# inverter.net
KiCad netlist of a schematic drawn in Altium Designer
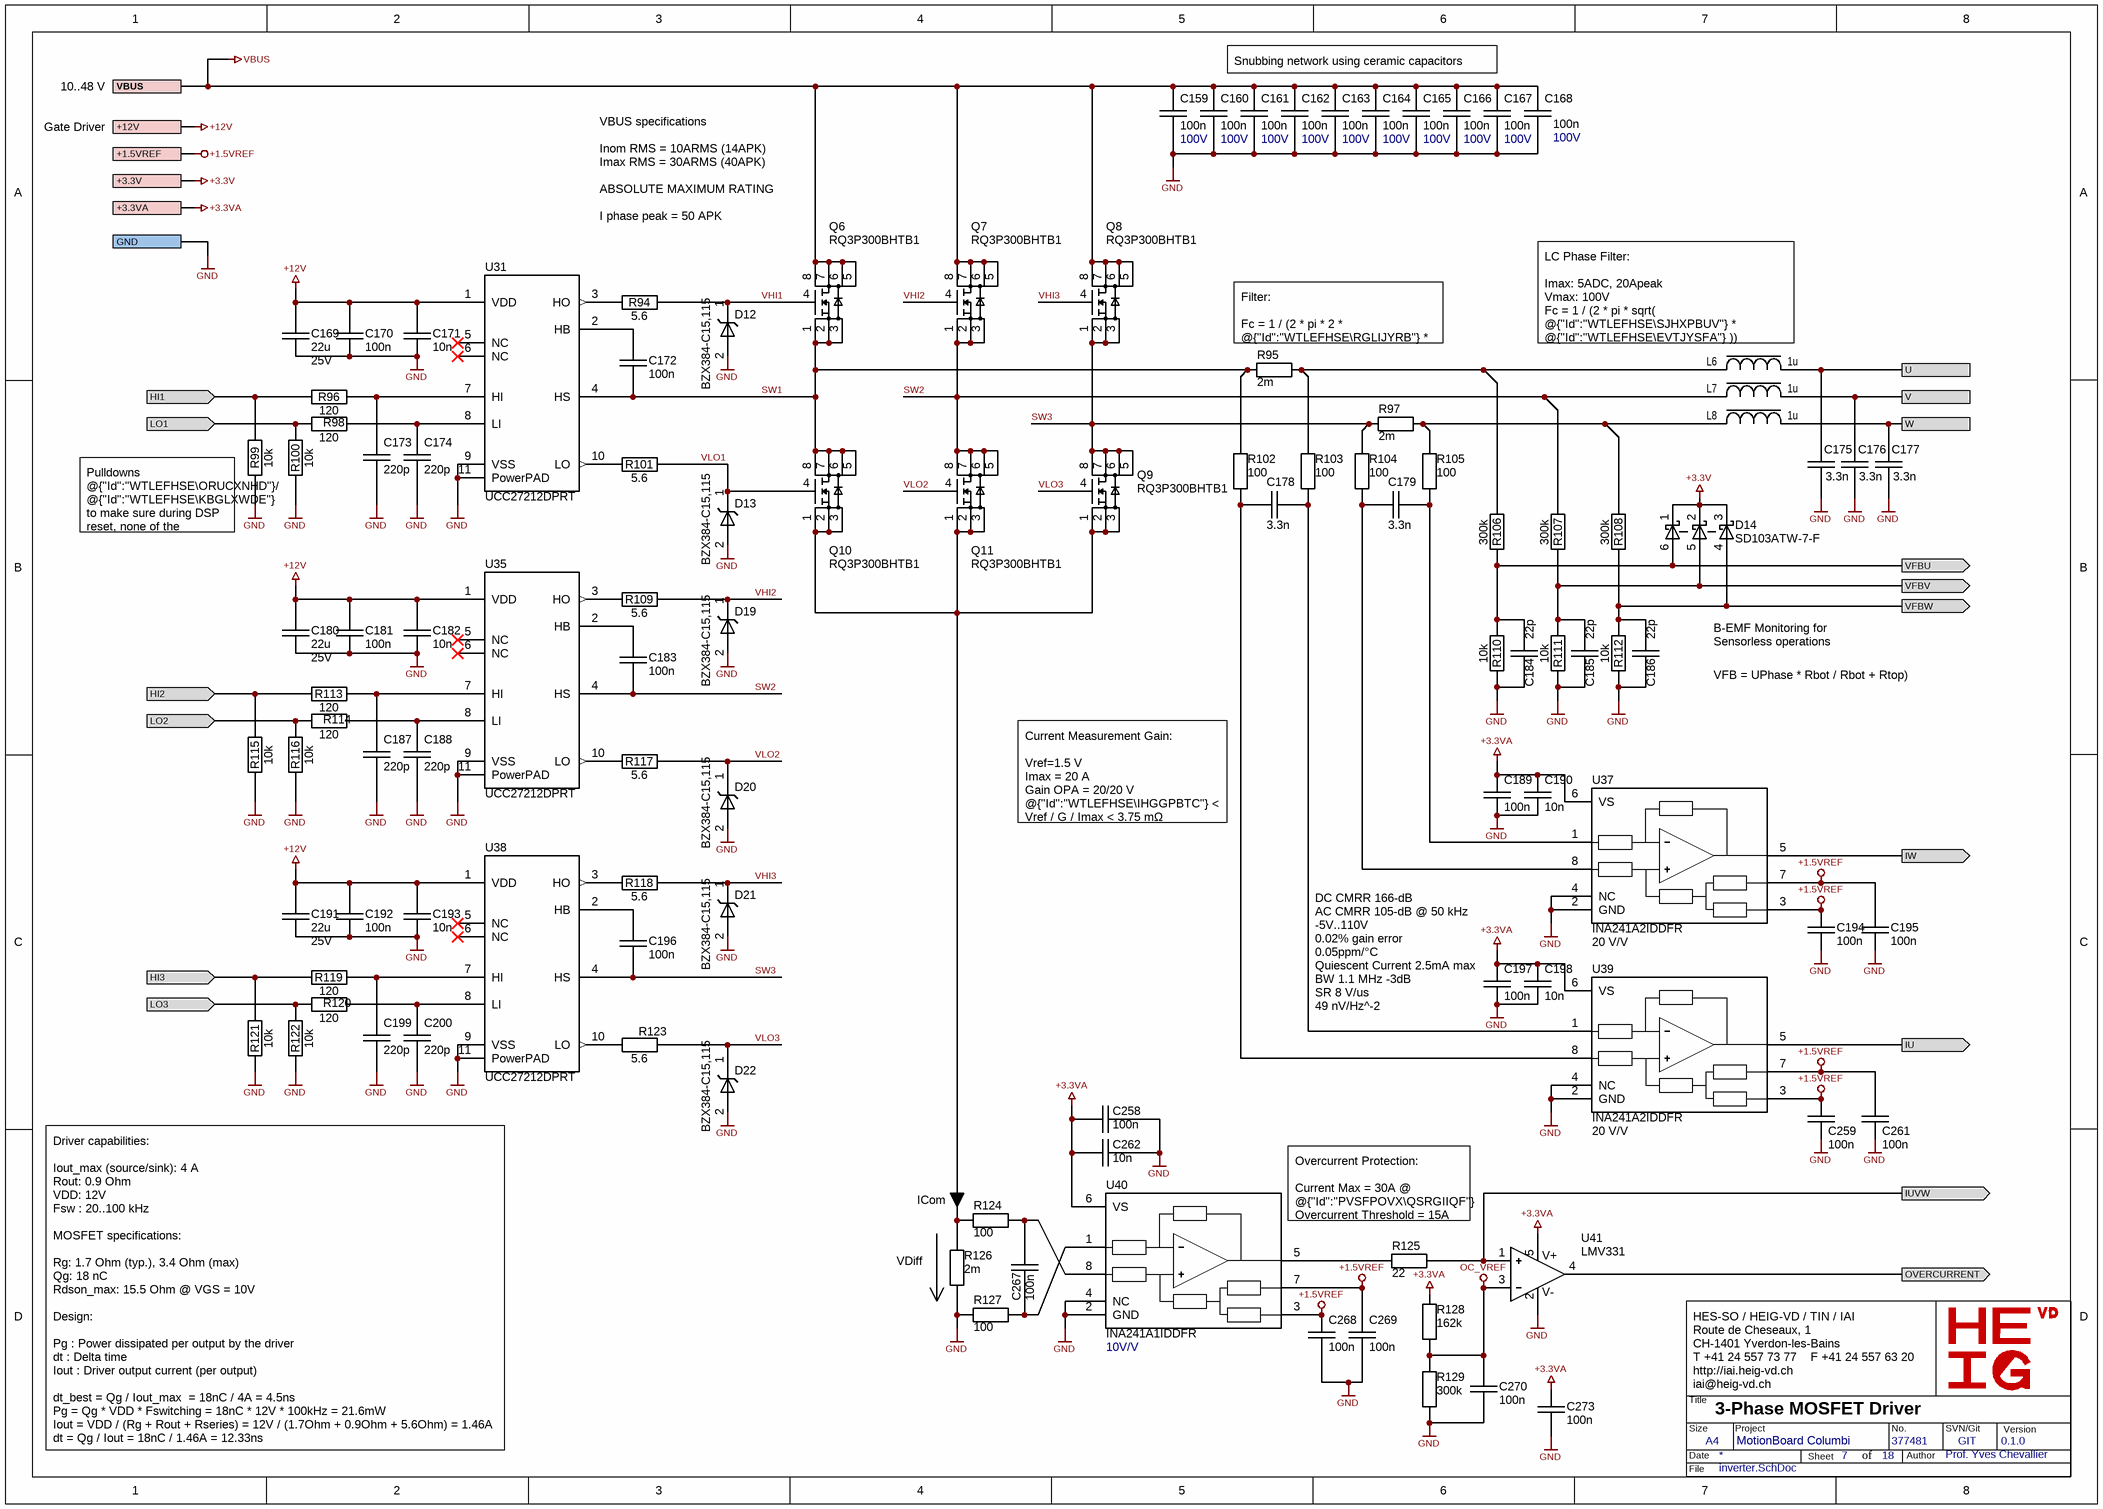
[diagram p0: inverter.SchDoc]

(export (version "E")
  (design (tool "Eeschema 10.0.6"))
  (components
    (comp (ref "C159")
      (value "100n")
      (footprint "SM/C1206")
      (description "100 nF ±5% 100V Ceramic Capacitor C0G, NP0 1206 (3216 Metric)")
      (fields (field (name "VOLTAGE") "100V"))
      (libsource (lib "motionboard") (part "CAP CER 100NF 100V C0G 1206"))
    )
    (comp (ref "C160")
      (value "100n")
      (footprint "SM/C1206")
      (description "100 nF ±5% 100V Ceramic Capacitor C0G, NP0 1206 (3216 Metric)")
      (fields (field (name "VOLTAGE") "100V"))
      (libsource (lib "motionboard") (part "CAP CER 100NF 100V C0G 1206"))
    )
    (comp (ref "C161")
      (value "100n")
      (footprint "SM/C1206")
      (description "100 nF ±5% 100V Ceramic Capacitor C0G, NP0 1206 (3216 Metric)")
      (fields (field (name "VOLTAGE") "100V"))
      (libsource (lib "motionboard") (part "CAP CER 100NF 100V C0G 1206"))
    )
    (comp (ref "C162")
      (value "100n")
      (footprint "SM/C1206")
      (description "100 nF ±5% 100V Ceramic Capacitor C0G, NP0 1206 (3216 Metric)")
      (fields (field (name "VOLTAGE") "100V"))
      (libsource (lib "motionboard") (part "CAP CER 100NF 100V C0G 1206"))
    )
    (comp (ref "C163")
      (value "100n")
      (footprint "SM/C1206")
      (description "100 nF ±5% 100V Ceramic Capacitor C0G, NP0 1206 (3216 Metric)")
      (fields (field (name "VOLTAGE") "100V"))
      (libsource (lib "motionboard") (part "CAP CER 100NF 100V C0G 1206"))
    )
    (comp (ref "C164")
      (value "100n")
      (footprint "SM/C1206")
      (description "100 nF ±5% 100V Ceramic Capacitor C0G, NP0 1206 (3216 Metric)")
      (fields (field (name "VOLTAGE") "100V"))
      (libsource (lib "motionboard") (part "CAP CER 100NF 100V C0G 1206"))
    )
    (comp (ref "C165")
      (value "100n")
      (footprint "SM/C1206")
      (description "100 nF ±5% 100V Ceramic Capacitor C0G, NP0 1206 (3216 Metric)")
      (fields (field (name "VOLTAGE") "100V"))
      (libsource (lib "motionboard") (part "CAP CER 100NF 100V C0G 1206"))
    )
    (comp (ref "C166")
      (value "100n")
      (footprint "SM/C1206")
      (description "100 nF ±5% 100V Ceramic Capacitor C0G, NP0 1206 (3216 Metric)")
      (fields (field (name "VOLTAGE") "100V"))
      (libsource (lib "motionboard") (part "CAP CER 100NF 100V C0G 1206"))
    )
    (comp (ref "C167")
      (value "100n")
      (footprint "SM/C1206")
      (description "100 nF ±5% 100V Ceramic Capacitor C0G, NP0 1206 (3216 Metric)")
      (fields (field (name "VOLTAGE") "100V"))
      (libsource (lib "motionboard") (part "CAP CER 100NF 100V C0G 1206"))
    )
    (comp (ref "C168")
      (value "100n")
      (footprint "SM/C1206")
      (description "100 nF ±5% 100V Ceramic Capacitor C0G, NP0 1206 (3216 Metric)")
      (fields (field (name "VOLTAGE") "100V"))
      (libsource (lib "motionboard") (part "CAP CER 100NF 100V C0G 1206"))
    )
    (comp (ref "C169")
      (value "22u")
      (footprint "SM/C0805")
      (description "22 µF ±20% 25V Ceramic Capacitor X5R 0805 (2012 Metric)")
      (fields (field (name "VOLTAGE") "25V"))
      (libsource (lib "motionboard") (part "CAP CER 22UF 25V X5R 0805"))
    )
    (comp (ref "C170")
      (value "100n")
      (footprint "SM/C0402")
      (description "100 nF ±10% 25V Ceramic Capacitor X5R 0402 (1005 Metric)")
      (fields (field (name "VOLTAGE") "25V"))
      (libsource (lib "motionboard") (part "CAP CER 100NF 25V X5R 0402"))
    )
    (comp (ref "C171")
      (value "10n")
      (footprint "SM/C0402")
      (description "10 nF ±10% 50V Ceramic Capacitor X7R 0402 (1005 Metric)")
      (fields (field (name "VOLTAGE") "50V"))
      (libsource (lib "motionboard") (part "CAP CER 10NF 50V X7R 0402"))
    )
    (comp (ref "C172")
      (value "100n")
      (footprint "SM/C0402")
      (description "100 nF ±10% 25V Ceramic Capacitor X5R 0402 (1005 Metric)")
      (fields (field (name "VOLTAGE") "25V"))
      (libsource (lib "motionboard") (part "CAP CER 100NF 25V X5R 0402"))
    )
    (comp (ref "C173")
      (value "220p")
      (footprint "SM/C0402")
      (description "220 pF ±5% 50V Ceramic Capacitor C0G, NP0 0402 (1005 Metric)")
      (fields (field (name "VOLTAGE") "50V"))
      (libsource (lib "motionboard") (part "CAP CER 220PF 50V C0G/NP0 0402"))
    )
    (comp (ref "C174")
      (value "220p")
      (footprint "SM/C0402")
      (description "220 pF ±5% 50V Ceramic Capacitor C0G, NP0 0402 (1005 Metric)")
      (fields (field (name "VOLTAGE") "50V"))
      (libsource (lib "motionboard") (part "CAP CER 220PF 50V C0G/NP0 0402"))
    )
    (comp (ref "C175")
      (value "3.3n")
      (footprint "SM/C0402")
      (description "3.3 nF ±10% 100V Ceramic Capacitor X8R 0402 (1005 Metric)")
      (fields (field (name "VOLTAGE") "16V"))
      (libsource (lib "motionboard") (part "CAP CER 3.3NF 100V X8R 0402"))
    )
    (comp (ref "C176")
      (value "3.3n")
      (footprint "SM/C0402")
      (description "3.3 nF ±10% 100V Ceramic Capacitor X8R 0402 (1005 Metric)")
      (fields (field (name "VOLTAGE") "16V"))
      (libsource (lib "motionboard") (part "CAP CER 3.3NF 100V X8R 0402"))
    )
    (comp (ref "C177")
      (value "3.3n")
      (footprint "SM/C0402")
      (description "3.3 nF ±10% 100V Ceramic Capacitor X8R 0402 (1005 Metric)")
      (fields (field (name "VOLTAGE") "16V"))
      (libsource (lib "motionboard") (part "CAP CER 3.3NF 100V X8R 0402"))
    )
    (comp (ref "C178")
      (value "3.3n")
      (footprint "SM/C0402")
      (description "3.3 nF ±10% 100V Ceramic Capacitor X8R 0402 (1005 Metric)")
      (fields (field (name "VOLTAGE") "16V"))
      (libsource (lib "motionboard") (part "CAP CER 3.3NF 100V X8R 0402"))
    )
    (comp (ref "C179")
      (value "3.3n")
      (footprint "SM/C0402")
      (description "3.3 nF ±10% 100V Ceramic Capacitor X8R 0402 (1005 Metric)")
      (fields (field (name "VOLTAGE") "16V"))
      (libsource (lib "motionboard") (part "CAP CER 3.3NF 100V X8R 0402"))
    )
    (comp (ref "C180")
      (value "22u")
      (footprint "SM/C0805")
      (description "22 µF ±20% 25V Ceramic Capacitor X5R 0805 (2012 Metric)")
      (fields (field (name "VOLTAGE") "25V"))
      (libsource (lib "motionboard") (part "CAP CER 22UF 25V X5R 0805"))
    )
    (comp (ref "C181")
      (value "100n")
      (footprint "SM/C0402")
      (description "100 nF ±10% 25V Ceramic Capacitor X5R 0402 (1005 Metric)")
      (fields (field (name "VOLTAGE") "25V"))
      (libsource (lib "motionboard") (part "CAP CER 100NF 25V X5R 0402"))
    )
    (comp (ref "C182")
      (value "10n")
      (footprint "SM/C0402")
      (description "10 nF ±10% 50V Ceramic Capacitor X7R 0402 (1005 Metric)")
      (fields (field (name "VOLTAGE") "50V"))
      (libsource (lib "motionboard") (part "CAP CER 10NF 50V X7R 0402"))
    )
    (comp (ref "C183")
      (value "100n")
      (footprint "SM/C0402")
      (description "100 nF ±10% 25V Ceramic Capacitor X5R 0402 (1005 Metric)")
      (fields (field (name "VOLTAGE") "25V"))
      (libsource (lib "motionboard") (part "CAP CER 100NF 25V X5R 0402"))
    )
    (comp (ref "C184")
      (value "22p")
      (footprint "SM/C0402")
      (description "22 pF ±2% 50V Ceramic Capacitor C0G, NP0 0402 (1005 Metric)")
      (fields (field (name "VOLTAGE") "50V"))
      (libsource (lib "motionboard") (part "CAP CER 22PF 50V C0G/NPO 0402"))
    )
    (comp (ref "C185")
      (value "22p")
      (footprint "SM/C0402")
      (description "22 pF ±2% 50V Ceramic Capacitor C0G, NP0 0402 (1005 Metric)")
      (fields (field (name "VOLTAGE") "50V"))
      (libsource (lib "motionboard") (part "CAP CER 22PF 50V C0G/NPO 0402"))
    )
    (comp (ref "C186")
      (value "22p")
      (footprint "SM/C0402")
      (description "22 pF ±2% 50V Ceramic Capacitor C0G, NP0 0402 (1005 Metric)")
      (fields (field (name "VOLTAGE") "50V"))
      (libsource (lib "motionboard") (part "CAP CER 22PF 50V C0G/NPO 0402"))
    )
    (comp (ref "C187")
      (value "220p")
      (footprint "SM/C0402")
      (description "220 pF ±5% 50V Ceramic Capacitor C0G, NP0 0402 (1005 Metric)")
      (fields (field (name "VOLTAGE") "50V"))
      (libsource (lib "motionboard") (part "CAP CER 220PF 50V C0G/NP0 0402"))
    )
    (comp (ref "C188")
      (value "220p")
      (footprint "SM/C0402")
      (description "220 pF ±5% 50V Ceramic Capacitor C0G, NP0 0402 (1005 Metric)")
      (fields (field (name "VOLTAGE") "50V"))
      (libsource (lib "motionboard") (part "CAP CER 220PF 50V C0G/NP0 0402"))
    )
    (comp (ref "C189")
      (value "100n")
      (footprint "SM/C0402")
      (description "100 nF ±10% 25V Ceramic Capacitor X5R 0402 (1005 Metric)")
      (fields (field (name "VOLTAGE") "25V"))
      (libsource (lib "motionboard") (part "CAP CER 100NF 25V X5R 0402"))
    )
    (comp (ref "C190")
      (value "10n")
      (footprint "SM/C0402")
      (description "10 nF ±10% 50V Ceramic Capacitor X7R 0402 (1005 Metric)")
      (fields (field (name "VOLTAGE") "50V"))
      (libsource (lib "motionboard") (part "CAP CER 10NF 50V X7R 0402"))
    )
    (comp (ref "C191")
      (value "22u")
      (footprint "SM/C0805")
      (description "22 µF ±20% 25V Ceramic Capacitor X5R 0805 (2012 Metric)")
      (fields (field (name "VOLTAGE") "25V"))
      (libsource (lib "motionboard") (part "CAP CER 22UF 25V X5R 0805"))
    )
    (comp (ref "C192")
      (value "100n")
      (footprint "SM/C0402")
      (description "100 nF ±10% 25V Ceramic Capacitor X5R 0402 (1005 Metric)")
      (fields (field (name "VOLTAGE") "25V"))
      (libsource (lib "motionboard") (part "CAP CER 100NF 25V X5R 0402"))
    )
    (comp (ref "C193")
      (value "10n")
      (footprint "SM/C0402")
      (description "10 nF ±10% 50V Ceramic Capacitor X7R 0402 (1005 Metric)")
      (fields (field (name "VOLTAGE") "50V"))
      (libsource (lib "motionboard") (part "CAP CER 10NF 50V X7R 0402"))
    )
    (comp (ref "C194")
      (value "100n")
      (footprint "SM/C0402")
      (description "100 nF ±10% 25V Ceramic Capacitor X5R 0402 (1005 Metric)")
      (fields (field (name "VOLTAGE") "25V"))
      (libsource (lib "motionboard") (part "CAP CER 100NF 25V X5R 0402"))
    )
    (comp (ref "C195")
      (value "100n")
      (footprint "SM/C0402")
      (description "100 nF ±10% 25V Ceramic Capacitor X5R 0402 (1005 Metric)")
      (fields (field (name "VOLTAGE") "25V"))
      (libsource (lib "motionboard") (part "CAP CER 100NF 25V X5R 0402"))
    )
    (comp (ref "C196")
      (value "100n")
      (footprint "SM/C0402")
      (description "100 nF ±10% 25V Ceramic Capacitor X5R 0402 (1005 Metric)")
      (fields (field (name "VOLTAGE") "25V"))
      (libsource (lib "motionboard") (part "CAP CER 100NF 25V X5R 0402"))
    )
    (comp (ref "C197")
      (value "100n")
      (footprint "SM/C0402")
      (description "100 nF ±10% 25V Ceramic Capacitor X5R 0402 (1005 Metric)")
      (fields (field (name "VOLTAGE") "25V"))
      (libsource (lib "motionboard") (part "CAP CER 100NF 25V X5R 0402"))
    )
    (comp (ref "C198")
      (value "10n")
      (footprint "SM/C0402")
      (description "10 nF ±10% 50V Ceramic Capacitor X7R 0402 (1005 Metric)")
      (fields (field (name "VOLTAGE") "50V"))
      (libsource (lib "motionboard") (part "CAP CER 10NF 50V X7R 0402"))
    )
    (comp (ref "C199")
      (value "220p")
      (footprint "SM/C0402")
      (description "220 pF ±5% 50V Ceramic Capacitor C0G, NP0 0402 (1005 Metric)")
      (fields (field (name "VOLTAGE") "50V"))
      (libsource (lib "motionboard") (part "CAP CER 220PF 50V C0G/NP0 0402"))
    )
    (comp (ref "C200")
      (value "220p")
      (footprint "SM/C0402")
      (description "220 pF ±5% 50V Ceramic Capacitor C0G, NP0 0402 (1005 Metric)")
      (fields (field (name "VOLTAGE") "50V"))
      (libsource (lib "motionboard") (part "CAP CER 220PF 50V C0G/NP0 0402"))
    )
    (comp (ref "C258")
      (value "100n")
      (footprint "SM/C0402")
      (description "100 nF ±10% 25V Ceramic Capacitor X5R 0402 (1005 Metric)")
      (fields (field (name "VOLTAGE") "25V"))
      (libsource (lib "motionboard") (part "CAP CER 100NF 25V X5R 0402"))
    )
    (comp (ref "C259")
      (value "100n")
      (footprint "SM/C0402")
      (description "100 nF ±10% 25V Ceramic Capacitor X5R 0402 (1005 Metric)")
      (fields (field (name "VOLTAGE") "25V"))
      (libsource (lib "motionboard") (part "CAP CER 100NF 25V X5R 0402"))
    )
    (comp (ref "C261")
      (value "100n")
      (footprint "SM/C0402")
      (description "100 nF ±10% 25V Ceramic Capacitor X5R 0402 (1005 Metric)")
      (fields (field (name "VOLTAGE") "25V"))
      (libsource (lib "motionboard") (part "CAP CER 100NF 25V X5R 0402"))
    )
    (comp (ref "C262")
      (value "10n")
      (footprint "SM/C0402")
      (description "10 nF ±10% 50V Ceramic Capacitor X7R 0402 (1005 Metric)")
      (fields (field (name "VOLTAGE") "50V"))
      (libsource (lib "motionboard") (part "CAP CER 10NF 50V X7R 0402"))
    )
    (comp (ref "C267")
      (value "100n")
      (footprint "SM/C0402")
      (description "100 nF ±10% 25V Ceramic Capacitor X5R 0402 (1005 Metric)")
      (fields (field (name "VOLTAGE") "25V"))
      (libsource (lib "motionboard") (part "CAP CER 100NF 25V X5R 0402"))
    )
    (comp (ref "C268")
      (value "100n")
      (footprint "SM/C0402")
      (description "100 nF ±10% 25V Ceramic Capacitor X5R 0402 (1005 Metric)")
      (fields (field (name "VOLTAGE") "25V"))
      (libsource (lib "motionboard") (part "CAP CER 100NF 25V X5R 0402"))
    )
    (comp (ref "C269")
      (value "100n")
      (footprint "SM/C0402")
      (description "100 nF ±10% 25V Ceramic Capacitor X5R 0402 (1005 Metric)")
      (fields (field (name "VOLTAGE") "25V"))
      (libsource (lib "motionboard") (part "CAP CER 100NF 25V X5R 0402"))
    )
    (comp (ref "C270")
      (value "100n")
      (footprint "SM/C0402")
      (description "100 nF ±10% 25V Ceramic Capacitor X5R 0402 (1005 Metric)")
      (fields (field (name "VOLTAGE") "25V"))
      (libsource (lib "motionboard") (part "CAP CER 100NF 25V X5R 0402"))
    )
    (comp (ref "C273")
      (value "100n")
      (footprint "SM/C0402")
      (description "100 nF ±10% 25V Ceramic Capacitor X5R 0402 (1005 Metric)")
      (fields (field (name "VOLTAGE") "25V"))
      (libsource (lib "motionboard") (part "CAP CER 100NF 25V X5R 0402"))
    )
    (comp (ref "D12")
      (value "BZX384-C15,115")
      (footprint "SODFL250X110-2N")
      (description "Zener Diode 15 V 300 mW ±5% Surface Mount SOD-323")
      (libsource (lib "motionboard") (part "DIODE ZENER 15V 300MW SOD323"))
    )
    (comp (ref "D13")
      (value "BZX384-C15,115")
      (footprint "SODFL250X110-2N")
      (description "Zener Diode 15 V 300 mW ±5% Surface Mount SOD-323")
      (libsource (lib "motionboard") (part "DIODE ZENER 15V 300MW SOD323"))
    )
    (comp (ref "D14")
      (value "SD103ATW-7-F")
      (footprint "SC70-6")
      (libsource (lib "motionboard") (part "SD103ATW-7-F"))
    )
    (comp (ref "D19")
      (value "BZX384-C15,115")
      (footprint "SODFL250X110-2N")
      (description "Zener Diode 15 V 300 mW ±5% Surface Mount SOD-323")
      (libsource (lib "motionboard") (part "DIODE ZENER 15V 300MW SOD323"))
    )
    (comp (ref "D20")
      (value "BZX384-C15,115")
      (footprint "SODFL250X110-2N")
      (description "Zener Diode 15 V 300 mW ±5% Surface Mount SOD-323")
      (libsource (lib "motionboard") (part "DIODE ZENER 15V 300MW SOD323"))
    )
    (comp (ref "D21")
      (value "BZX384-C15,115")
      (footprint "SODFL250X110-2N")
      (description "Zener Diode 15 V 300 mW ±5% Surface Mount SOD-323")
      (libsource (lib "motionboard") (part "DIODE ZENER 15V 300MW SOD323"))
    )
    (comp (ref "D22")
      (value "BZX384-C15,115")
      (footprint "SODFL250X110-2N")
      (description "Zener Diode 15 V 300 mW ±5% Surface Mount SOD-323")
      (libsource (lib "motionboard") (part "DIODE ZENER 15V 300MW SOD323"))
    )
    (comp (ref "L6")
      (value "1u")
      (footprint "PA5005.102NLT")
      (description "1 µH Shielded Molded Inductor 20 A 4.52mOhm Max Nonstandard")
      (libsource (lib "motionboard") (part "PA5005.102NLT"))
    )
    (comp (ref "L7")
      (value "1u")
      (footprint "PA5005.102NLT")
      (description "1 µH Shielded Molded Inductor 20 A 4.52mOhm Max Nonstandard")
      (libsource (lib "motionboard") (part "PA5005.102NLT"))
    )
    (comp (ref "L8")
      (value "1u")
      (footprint "PA5005.102NLT")
      (description "1 µH Shielded Molded Inductor 20 A 4.52mOhm Max Nonstandard")
      (libsource (lib "motionboard") (part "PA5005.102NLT"))
    )
    (comp (ref "Q6")
      (value "RQ3P300BHTB1")
      (footprint "RQ3P300BHTB1")
      (description "N-Channel 100 V 39A (Ta) 2W (Ta) Surface Mount 8-HSMT (3.2x3)")
      (libsource (lib "motionboard") (part "RQ3P300BHTB1"))
    )
    (comp (ref "Q7")
      (value "RQ3P300BHTB1")
      (footprint "RQ3P300BHTB1")
      (description "N-Channel 100 V 39A (Ta) 2W (Ta) Surface Mount 8-HSMT (3.2x3)")
      (libsource (lib "motionboard") (part "RQ3P300BHTB1"))
    )
    (comp (ref "Q8")
      (value "RQ3P300BHTB1")
      (footprint "RQ3P300BHTB1")
      (description "N-Channel 100 V 39A (Ta) 2W (Ta) Surface Mount 8-HSMT (3.2x3)")
      (libsource (lib "motionboard") (part "RQ3P300BHTB1"))
    )
    (comp (ref "Q9")
      (value "RQ3P300BHTB1")
      (footprint "RQ3P300BHTB1")
      (description "N-Channel 100 V 39A (Ta) 2W (Ta) Surface Mount 8-HSMT (3.2x3)")
      (libsource (lib "motionboard") (part "RQ3P300BHTB1"))
    )
    (comp (ref "Q10")
      (value "RQ3P300BHTB1")
      (footprint "RQ3P300BHTB1")
      (description "N-Channel 100 V 39A (Ta) 2W (Ta) Surface Mount 8-HSMT (3.2x3)")
      (libsource (lib "motionboard") (part "RQ3P300BHTB1"))
    )
    (comp (ref "Q11")
      (value "RQ3P300BHTB1")
      (footprint "RQ3P300BHTB1")
      (description "N-Channel 100 V 39A (Ta) 2W (Ta) Surface Mount 8-HSMT (3.2x3)")
      (libsource (lib "motionboard") (part "RQ3P300BHTB1"))
    )
    (comp (ref "R94")
      (value "5.6")
      (footprint "SM/R0402")
      (description "5.6 Ohms ±5% 0.063W, 1/16W Chip Resistor 0402 (1005 Metric) Moisture Resistant Thick Film")
      (libsource (lib "motionboard") (part "RES 5.6 OHM 5% 1/16W 0402"))
    )
    (comp (ref "R95")
      (value "2m")
      (footprint "SM/R1206")
      (description "2 mOhms ±1% 1W Chip Resistor 1206 (3216 Metric) Current Sense, Moisture Resistant Metal Element")
      (libsource (lib "motionboard") (part "RES 0.002 OHM 1% 1W 1206"))
    )
    (comp (ref "R96")
      (value "120")
      (footprint "SM/R0402")
      (description "120 Ohms ±1% 0.063W, 1/16W Chip Resistor 0402 (1005 Metric) Moisture Resistant Thick Film")
      (libsource (lib "motionboard") (part "RES 120 OHM 1% 1/16W 0402"))
    )
    (comp (ref "R97")
      (value "2m")
      (footprint "SM/R1206")
      (description "2 mOhms ±1% 1W Chip Resistor 1206 (3216 Metric) Current Sense, Moisture Resistant Metal Element")
      (libsource (lib "motionboard") (part "RES 0.002 OHM 1% 1W 1206"))
    )
    (comp (ref "R98")
      (value "120")
      (footprint "SM/R0402")
      (description "120 Ohms ±1% 0.063W, 1/16W Chip Resistor 0402 (1005 Metric) Moisture Resistant Thick Film")
      (libsource (lib "motionboard") (part "RES 120 OHM 1% 1/16W 0402"))
    )
    (comp (ref "R99")
      (value "10k")
      (footprint "SM/R0402")
      (description "10 kOhms ±1% 0.063W, 1/16W Chip Resistor 0402 (1005 Metric) Moisture Resistant Thick Film")
      (libsource (lib "") (part "RES 10K OHM 1% 1/16W 0402_1"))
    )
    (comp (ref "R100")
      (value "10k")
      (footprint "SM/R0402")
      (description "10 kOhms ±1% 0.063W, 1/16W Chip Resistor 0402 (1005 Metric) Moisture Resistant Thick Film")
      (libsource (lib "") (part "RES 10K OHM 1% 1/16W 0402_1"))
    )
    (comp (ref "R101")
      (value "5.6")
      (footprint "SM/R0402")
      (description "5.6 Ohms ±5% 0.063W, 1/16W Chip Resistor 0402 (1005 Metric) Moisture Resistant Thick Film")
      (libsource (lib "") (part "RES 5.6 OHM 5% 1/16W 0402_1"))
    )
    (comp (ref "R102")
      (value "100")
      (footprint "SM/R0402")
      (description "100 Ohms ±1% 0.063W, 1/16W Chip Resistor 0402 (1005 Metric) Moisture Resistant Thick Film")
      (libsource (lib "") (part "RES 100 OHM 1% 1/16W 0402_1"))
    )
    (comp (ref "R103")
      (value "100")
      (footprint "SM/R0402")
      (description "100 Ohms ±1% 0.063W, 1/16W Chip Resistor 0402 (1005 Metric) Moisture Resistant Thick Film")
      (libsource (lib "") (part "RES 100 OHM 1% 1/16W 0402_1"))
    )
    (comp (ref "R104")
      (value "100")
      (footprint "SM/R0402")
      (description "100 Ohms ±1% 0.063W, 1/16W Chip Resistor 0402 (1005 Metric) Moisture Resistant Thick Film")
      (libsource (lib "") (part "RES 100 OHM 1% 1/16W 0402_1"))
    )
    (comp (ref "R105")
      (value "100")
      (footprint "SM/R0402")
      (description "100 Ohms ±1% 0.063W, 1/16W Chip Resistor 0402 (1005 Metric) Moisture Resistant Thick Film")
      (libsource (lib "") (part "RES 100 OHM 1% 1/16W 0402_1"))
    )
    (comp (ref "R106")
      (value "300k")
      (footprint "SM/R0402")
      (description "300 kOhms ±1% 0.063W, 1/16W Chip Resistor 0402 (1005 Metric) Moisture Resistant Thick Film")
      (libsource (lib "motionboard") (part "RES 300K OHM 1% 1/16W 0402"))
    )
    (comp (ref "R107")
      (value "300k")
      (footprint "SM/R0402")
      (description "300 kOhms ±1% 0.063W, 1/16W Chip Resistor 0402 (1005 Metric) Moisture Resistant Thick Film")
      (libsource (lib "motionboard") (part "RES 300K OHM 1% 1/16W 0402"))
    )
    (comp (ref "R108")
      (value "300k")
      (footprint "SM/R0402")
      (description "300 kOhms ±1% 0.063W, 1/16W Chip Resistor 0402 (1005 Metric) Moisture Resistant Thick Film")
      (libsource (lib "motionboard") (part "RES 300K OHM 1% 1/16W 0402"))
    )
    (comp (ref "R109")
      (value "5.6")
      (footprint "SM/R0402")
      (description "5.6 Ohms ±5% 0.063W, 1/16W Chip Resistor 0402 (1005 Metric) Moisture Resistant Thick Film")
      (libsource (lib "motionboard") (part "RES 5.6 OHM 5% 1/16W 0402"))
    )
    (comp (ref "R110")
      (value "10k")
      (footprint "SM/R0402")
      (description "10 kOhms ±1% 0.063W, 1/16W Chip Resistor 0402 (1005 Metric) Moisture Resistant Thick Film")
      (libsource (lib "motionboard") (part "RES 10K OHM 1% 1/16W 0402"))
    )
    (comp (ref "R111")
      (value "10k")
      (footprint "SM/R0402")
      (description "10 kOhms ±1% 0.063W, 1/16W Chip Resistor 0402 (1005 Metric) Moisture Resistant Thick Film")
      (libsource (lib "motionboard") (part "RES 10K OHM 1% 1/16W 0402"))
    )
    (comp (ref "R112")
      (value "10k")
      (footprint "SM/R0402")
      (description "10 kOhms ±1% 0.063W, 1/16W Chip Resistor 0402 (1005 Metric) Moisture Resistant Thick Film")
      (libsource (lib "motionboard") (part "RES 10K OHM 1% 1/16W 0402"))
    )
    (comp (ref "R113")
      (value "120")
      (footprint "SM/R0402")
      (description "120 Ohms ±1% 0.063W, 1/16W Chip Resistor 0402 (1005 Metric) Moisture Resistant Thick Film")
      (libsource (lib "motionboard") (part "RES 120 OHM 1% 1/16W 0402"))
    )
    (comp (ref "R114")
      (value "120")
      (footprint "SM/R0402")
      (description "120 Ohms ±1% 0.063W, 1/16W Chip Resistor 0402 (1005 Metric) Moisture Resistant Thick Film")
      (libsource (lib "motionboard") (part "RES 120 OHM 1% 1/16W 0402"))
    )
    (comp (ref "R115")
      (value "10k")
      (footprint "SM/R0402")
      (description "10 kOhms ±1% 0.063W, 1/16W Chip Resistor 0402 (1005 Metric) Moisture Resistant Thick Film")
      (libsource (lib "") (part "RES 10K OHM 1% 1/16W 0402_1"))
    )
    (comp (ref "R116")
      (value "10k")
      (footprint "SM/R0402")
      (description "10 kOhms ±1% 0.063W, 1/16W Chip Resistor 0402 (1005 Metric) Moisture Resistant Thick Film")
      (libsource (lib "") (part "RES 10K OHM 1% 1/16W 0402_1"))
    )
    (comp (ref "R117")
      (value "5.6")
      (footprint "SM/R0402")
      (description "5.6 Ohms ±5% 0.063W, 1/16W Chip Resistor 0402 (1005 Metric) Moisture Resistant Thick Film")
      (libsource (lib "") (part "RES 5.6 OHM 5% 1/16W 0402_1"))
    )
    (comp (ref "R118")
      (value "5.6")
      (footprint "SM/R0402")
      (description "5.6 Ohms ±5% 0.063W, 1/16W Chip Resistor 0402 (1005 Metric) Moisture Resistant Thick Film")
      (libsource (lib "motionboard") (part "RES 5.6 OHM 5% 1/16W 0402"))
    )
    (comp (ref "R119")
      (value "120")
      (footprint "SM/R0402")
      (description "120 Ohms ±1% 0.063W, 1/16W Chip Resistor 0402 (1005 Metric) Moisture Resistant Thick Film")
      (libsource (lib "motionboard") (part "RES 120 OHM 1% 1/16W 0402"))
    )
    (comp (ref "R120")
      (value "120")
      (footprint "SM/R0402")
      (description "120 Ohms ±1% 0.063W, 1/16W Chip Resistor 0402 (1005 Metric) Moisture Resistant Thick Film")
      (libsource (lib "motionboard") (part "RES 120 OHM 1% 1/16W 0402"))
    )
    (comp (ref "R121")
      (value "10k")
      (footprint "SM/R0402")
      (description "10 kOhms ±1% 0.063W, 1/16W Chip Resistor 0402 (1005 Metric) Moisture Resistant Thick Film")
      (libsource (lib "") (part "RES 10K OHM 1% 1/16W 0402_1"))
    )
    (comp (ref "R122")
      (value "10k")
      (footprint "SM/R0402")
      (description "10 kOhms ±1% 0.063W, 1/16W Chip Resistor 0402 (1005 Metric) Moisture Resistant Thick Film")
      (libsource (lib "") (part "RES 10K OHM 1% 1/16W 0402_1"))
    )
    (comp (ref "R123")
      (value "5.6")
      (footprint "SM/R0402")
      (description "5.6 Ohms ±5% 0.063W, 1/16W Chip Resistor 0402 (1005 Metric) Moisture Resistant Thick Film")
      (libsource (lib "") (part "RES 5.6 OHM 5% 1/16W 0402_1"))
    )
    (comp (ref "R124")
      (value "100")
      (footprint "SM/R0402")
      (description "100 Ohms ±1% 0.063W, 1/16W Chip Resistor 0402 (1005 Metric) Moisture Resistant Thick Film")
      (libsource (lib "motionboard") (part "RES 100 OHM 1% 1/16W 0402"))
    )
    (comp (ref "R125")
      (value "22")
      (footprint "SM/R0402")
      (description "22 Ohms ±1% 0.063W, 1/16W Chip Resistor 0402 (1005 Metric) Moisture Resistant Thick Film")
      (libsource (lib "motionboard") (part "RES 22 OHM 1% 1/16W 0402"))
    )
    (comp (ref "R126")
      (value "2m")
      (footprint "SM/R1206")
      (description "2 mOhms ±1% 1W Chip Resistor 1206 (3216 Metric) Current Sense, Moisture Resistant Metal Element")
      (libsource (lib "") (part "RES 0.002 OHM 1% 1W 1206_1"))
    )
    (comp (ref "R127")
      (value "100")
      (footprint "SM/R0402")
      (description "100 Ohms ±1% 0.063W, 1/16W Chip Resistor 0402 (1005 Metric) Moisture Resistant Thick Film")
      (libsource (lib "motionboard") (part "RES 100 OHM 1% 1/16W 0402"))
    )
    (comp (ref "R128")
      (value "162k")
      (footprint "SM/R0402")
      (description "162 kOhms ±1% 0.063W, 1/16W Chip Resistor 0402 (1005 Metric) Moisture Resistant Thick Film")
      (libsource (lib "motionboard") (part "RES 162K OHM 1% 1/16W 0402"))
    )
    (comp (ref "R129")
      (value "300k")
      (footprint "SM/R0402")
      (description "300 kOhms ±1% 0.063W, 1/16W Chip Resistor 0402 (1005 Metric) Moisture Resistant Thick Film")
      (libsource (lib "motionboard") (part "RES 300K OHM 1% 1/16W 0402"))
    )
    (comp (ref "U31")
      (value "UCC27212DPRT")
      (footprint "PSON80P400X80_HS-11N")
      (description "Half-Bridge Gate Driver IC Non-Inverting 10-WSON (4x4)")
      (libsource (lib "motionboard") (part "UCC27212"))
    )
    (comp (ref "U35")
      (value "UCC27212DPRT")
      (footprint "PSON80P400X80_HS-11N")
      (description "Half-Bridge Gate Driver IC Non-Inverting 10-WSON (4x4)")
      (libsource (lib "motionboard") (part "UCC27212"))
    )
    (comp (ref "U37")
      (value "INA241A2IDDFR")
      (footprint "SOT65P280X110-8N")
      (description "Current Sense Amplifier 1 Circuit Single-Ended TSOT-23-8")
      (fields (field (name "GAIN") "20 V/V"))
      (libsource (lib "motionboard") (part "INA241A2IDDFR"))
    )
    (comp (ref "U38")
      (value "UCC27212DPRT")
      (footprint "PSON80P400X80_HS-11N")
      (description "Half-Bridge Gate Driver IC Non-Inverting 10-WSON (4x4)")
      (libsource (lib "motionboard") (part "UCC27212"))
    )
    (comp (ref "U39")
      (value "INA241A2IDDFR")
      (footprint "SOT65P280X110-8N")
      (description "Current Sense Amplifier 1 Circuit Single-Ended TSOT-23-8")
      (fields (field (name "GAIN") "20 V/V"))
      (libsource (lib "motionboard") (part "INA241A2IDDFR"))
    )
    (comp (ref "U40")
      (value "INA241A1IDDFR")
      (footprint "SOT65P280X110-8N")
      (description "Current Sense Amplifier 10V/V  1 Circuit Single-Ended TSOT-23-8")
      (fields (field (name "GAIN") "10V/V"))
      (libsource (lib "motionboard") (part "INA241A1IDDFR"))
    )
    (comp (ref "U41")
      (value "LMV331")
      (footprint "SOT23-5")
      (description "Comparator General Purpose CMOS, Open-Collector, TTL SOT-23-5")
      (libsource (lib "motionboard") (part "LM331"))
    )
  )
  (nets
    (net (code "1") (name "+1.5VREF") (class "Default")
      (node (ref "C194") (pin "2") (pintype "passive"))
      (node (ref "C195") (pin "2") (pintype "passive"))
      (node (ref "C259") (pin "2") (pintype "passive"))
      (node (ref "C261") (pin "2") (pintype "passive"))
      (node (ref "C268") (pin "2") (pintype "passive"))
      (node (ref "C269") (pin "2") (pintype "passive"))
      (node (ref "U37") (pin "3") (pinfunction "REF2_3") (pintype "passive"))
      (node (ref "U37") (pin "7") (pinfunction "REF1_7") (pintype "passive"))
      (node (ref "U39") (pin "3") (pinfunction "REF2_3") (pintype "passive"))
      (node (ref "U39") (pin "7") (pinfunction "REF1_7") (pintype "passive"))
      (node (ref "U40") (pin "3") (pinfunction "REF2_3") (pintype "passive"))
      (node (ref "U40") (pin "7") (pinfunction "REF1_7") (pintype "passive"))
    )
    (net (code "2") (name "+3.3V") (class "Default")
      (node (ref "D14") (pin "1") (pinfunction "K_1") (pintype "passive"))
      (node (ref "D14") (pin "2") (pinfunction "K_2") (pintype "passive"))
      (node (ref "D14") (pin "3") (pinfunction "K_3") (pintype "passive"))
    )
    (net (code "3") (name "+3.3VA") (class "Default")
      (node (ref "C189") (pin "2") (pintype "passive"))
      (node (ref "C190") (pin "1") (pintype "passive"))
      (node (ref "C197") (pin "2") (pintype "passive"))
      (node (ref "C198") (pin "1") (pintype "passive"))
      (node (ref "C258") (pin "2") (pintype "passive"))
      (node (ref "C262") (pin "1") (pintype "passive"))
      (node (ref "C273") (pin "2") (pintype "passive"))
      (node (ref "R128") (pin "2") (pintype "passive"))
      (node (ref "U37") (pin "6") (pinfunction "VS_6") (pintype "passive"))
      (node (ref "U39") (pin "6") (pinfunction "VS_6") (pintype "passive"))
      (node (ref "U40") (pin "6") (pinfunction "VS_6") (pintype "passive"))
      (node (ref "U41") (pin "5") (pinfunction "V+_5") (pintype "passive"))
    )
    (net (code "4") (name "+12V") (class "Default")
      (node (ref "C169") (pin "2") (pintype "passive"))
      (node (ref "C170") (pin "2") (pintype "passive"))
      (node (ref "C171") (pin "1") (pintype "passive"))
      (node (ref "C180") (pin "2") (pintype "passive"))
      (node (ref "C181") (pin "2") (pintype "passive"))
      (node (ref "C182") (pin "1") (pintype "passive"))
      (node (ref "C191") (pin "2") (pintype "passive"))
      (node (ref "C192") (pin "2") (pintype "passive"))
      (node (ref "C193") (pin "1") (pintype "passive"))
      (node (ref "U31") (pin "1") (pinfunction "VDD_1") (pintype "power_in"))
      (node (ref "U35") (pin "1") (pinfunction "VDD_1") (pintype "power_in"))
      (node (ref "U38") (pin "1") (pinfunction "VDD_1") (pintype "power_in"))
    )
    (net (code "5") (name "/HI1") (class "Default")
      (node (ref "R96") (pin "2") (pintype "passive"))
      (node (ref "R99") (pin "1") (pintype "passive"))
    )
    (net (code "6") (name "/HI2") (class "Default")
      (node (ref "R113") (pin "2") (pintype "passive"))
      (node (ref "R115") (pin "1") (pintype "passive"))
    )
    (net (code "7") (name "/HI3") (class "Default")
      (node (ref "R119") (pin "2") (pintype "passive"))
      (node (ref "R121") (pin "1") (pintype "passive"))
    )
    (net (code "8") (name "/IU") (class "Default")
      (node (ref "U39") (pin "5") (pinfunction "OUT_5") (pintype "passive"))
    )
    (net (code "9") (name "/IUVW") (class "Default")
      (node (ref "R125") (pin "1") (pintype "passive"))
      (node (ref "U41") (pin "1") (pinfunction "IN+_1") (pintype "passive"))
    )
    (net (code "10") (name "/IW") (class "Default")
      (node (ref "U37") (pin "5") (pinfunction "OUT_5") (pintype "passive"))
    )
    (net (code "11") (name "/LO1") (class "Default")
      (node (ref "R100") (pin "1") (pintype "passive"))
      (node (ref "R98") (pin "2") (pintype "passive"))
    )
    (net (code "12") (name "/LO2") (class "Default")
      (node (ref "R114") (pin "2") (pintype "passive"))
      (node (ref "R116") (pin "1") (pintype "passive"))
    )
    (net (code "13") (name "/LO3") (class "Default")
      (node (ref "R120") (pin "2") (pintype "passive"))
      (node (ref "R122") (pin "1") (pintype "passive"))
    )
    (net (code "14") (name "/OVERCURRENT") (class "Default")
      (node (ref "U41") (pin "4") (pinfunction "OUT_4") (pintype "passive"))
    )
    (net (code "15") (name "/SW1") (class "Default")
      (node (ref "C172") (pin "2") (pintype "passive"))
      (node (ref "Q10") (pin "5") (pinfunction "D_5") (pintype "passive"))
      (node (ref "Q10") (pin "6") (pinfunction "D_6") (pintype "passive"))
      (node (ref "Q10") (pin "7") (pinfunction "D_7") (pintype "passive"))
      (node (ref "Q10") (pin "8") (pinfunction "D_8") (pintype "passive"))
      (node (ref "Q6") (pin "1") (pinfunction "S_1") (pintype "passive"))
      (node (ref "Q6") (pin "2") (pinfunction "S_2") (pintype "passive"))
      (node (ref "Q6") (pin "3") (pinfunction "S_3") (pintype "passive"))
      (node (ref "R102") (pin "2") (pintype "passive"))
      (node (ref "R95") (pin "1") (pintype "passive"))
      (node (ref "U31") (pin "4") (pinfunction "HS_4") (pintype "power_in"))
    )
    (net (code "16") (name "/SW2") (class "Default")
      (node (ref "C183") (pin "2") (pintype "passive"))
      (node (ref "L7") (pin "1") (pintype "passive"))
      (node (ref "Q11") (pin "5") (pinfunction "D_5") (pintype "passive"))
      (node (ref "Q11") (pin "6") (pinfunction "D_6") (pintype "passive"))
      (node (ref "Q11") (pin "7") (pinfunction "D_7") (pintype "passive"))
      (node (ref "Q11") (pin "8") (pinfunction "D_8") (pintype "passive"))
      (node (ref "Q7") (pin "1") (pinfunction "S_1") (pintype "passive"))
      (node (ref "Q7") (pin "2") (pinfunction "S_2") (pintype "passive"))
      (node (ref "Q7") (pin "3") (pinfunction "S_3") (pintype "passive"))
      (node (ref "R107") (pin "2") (pintype "passive"))
      (node (ref "U35") (pin "4") (pinfunction "HS_4") (pintype "power_in"))
    )
    (net (code "17") (name "/SW3") (class "Default")
      (node (ref "C196") (pin "2") (pintype "passive"))
      (node (ref "Q8") (pin "1") (pinfunction "S_1") (pintype "passive"))
      (node (ref "Q8") (pin "2") (pinfunction "S_2") (pintype "passive"))
      (node (ref "Q8") (pin "3") (pinfunction "S_3") (pintype "passive"))
      (node (ref "Q9") (pin "5") (pinfunction "D_5") (pintype "passive"))
      (node (ref "Q9") (pin "6") (pinfunction "D_6") (pintype "passive"))
      (node (ref "Q9") (pin "7") (pinfunction "D_7") (pintype "passive"))
      (node (ref "Q9") (pin "8") (pinfunction "D_8") (pintype "passive"))
      (node (ref "R104") (pin "2") (pintype "passive"))
      (node (ref "R97") (pin "1") (pintype "passive"))
      (node (ref "U38") (pin "4") (pinfunction "HS_4") (pintype "power_in"))
    )
    (net (code "18") (name "/U") (class "Default")
      (node (ref "C175") (pin "2") (pintype "passive"))
      (node (ref "L6") (pin "2") (pintype "passive"))
    )
    (net (code "19") (name "/V") (class "Default")
      (node (ref "C176") (pin "2") (pintype "passive"))
      (node (ref "L7") (pin "2") (pintype "passive"))
    )
    (net (code "20") (name "/VFBU") (class "Default")
      (node (ref "C184") (pin "2") (pintype "passive"))
      (node (ref "D14") (pin "6") (pinfunction "A_6") (pintype "passive"))
      (node (ref "R106") (pin "1") (pintype "passive"))
      (node (ref "R110") (pin "2") (pintype "passive"))
    )
    (net (code "21") (name "/VFBV") (class "Default")
      (node (ref "C185") (pin "2") (pintype "passive"))
      (node (ref "D14") (pin "5") (pinfunction "A_5") (pintype "passive"))
      (node (ref "R107") (pin "1") (pintype "passive"))
      (node (ref "R111") (pin "2") (pintype "passive"))
    )
    (net (code "22") (name "/VFBW") (class "Default")
      (node (ref "C186") (pin "2") (pintype "passive"))
      (node (ref "D14") (pin "4") (pinfunction "A_4") (pintype "passive"))
      (node (ref "R108") (pin "1") (pintype "passive"))
      (node (ref "R112") (pin "2") (pintype "passive"))
    )
    (net (code "23") (name "/VHI1") (class "Default")
      (node (ref "D12") (pin "1") (pinfunction "K_1") (pintype "passive"))
      (node (ref "Q6") (pin "4") (pinfunction "G_4") (pintype "passive"))
      (node (ref "R94") (pin "2") (pintype "passive"))
    )
    (net (code "24") (name "/VHI2") (class "Default")
      (node (ref "D19") (pin "1") (pinfunction "K_1") (pintype "passive"))
      (node (ref "Q7") (pin "4") (pinfunction "G_4") (pintype "passive"))
      (node (ref "R109") (pin "2") (pintype "passive"))
    )
    (net (code "25") (name "/VHI3") (class "Default")
      (node (ref "D21") (pin "1") (pinfunction "K_1") (pintype "passive"))
      (node (ref "Q8") (pin "4") (pinfunction "G_4") (pintype "passive"))
      (node (ref "R118") (pin "2") (pintype "passive"))
    )
    (net (code "26") (name "/VLO1") (class "Default")
      (node (ref "D13") (pin "1") (pinfunction "K_1") (pintype "passive"))
      (node (ref "Q10") (pin "4") (pinfunction "G_4") (pintype "passive"))
      (node (ref "R101") (pin "1") (pintype "passive"))
    )
    (net (code "27") (name "/VLO2") (class "Default")
      (node (ref "D20") (pin "1") (pinfunction "K_1") (pintype "passive"))
      (node (ref "Q11") (pin "4") (pinfunction "G_4") (pintype "passive"))
      (node (ref "R117") (pin "1") (pintype "passive"))
    )
    (net (code "28") (name "/VLO3") (class "Default")
      (node (ref "D22") (pin "1") (pinfunction "K_1") (pintype "passive"))
      (node (ref "Q9") (pin "4") (pinfunction "G_4") (pintype "passive"))
      (node (ref "R123") (pin "1") (pintype "passive"))
    )
    (net (code "29") (name "/W") (class "Default")
      (node (ref "C177") (pin "2") (pintype "passive"))
      (node (ref "L8") (pin "2") (pintype "passive"))
    )
    (net (code "30") (name "GND") (class "Default")
      (node (ref "C159") (pin "1") (pintype "passive"))
      (node (ref "C160") (pin "1") (pintype "passive"))
      (node (ref "C161") (pin "1") (pintype "passive"))
      (node (ref "C162") (pin "1") (pintype "passive"))
      (node (ref "C163") (pin "1") (pintype "passive"))
      (node (ref "C164") (pin "1") (pintype "passive"))
      (node (ref "C165") (pin "1") (pintype "passive"))
      (node (ref "C166") (pin "1") (pintype "passive"))
      (node (ref "C167") (pin "1") (pintype "passive"))
      (node (ref "C168") (pin "1") (pintype "passive"))
      (node (ref "C169") (pin "1") (pintype "passive"))
      (node (ref "C170") (pin "1") (pintype "passive"))
      (node (ref "C171") (pin "2") (pintype "passive"))
      (node (ref "C173") (pin "1") (pintype "passive"))
      (node (ref "C174") (pin "1") (pintype "passive"))
      (node (ref "C175") (pin "1") (pintype "passive"))
      (node (ref "C176") (pin "1") (pintype "passive"))
      (node (ref "C177") (pin "1") (pintype "passive"))
      (node (ref "C180") (pin "1") (pintype "passive"))
      (node (ref "C181") (pin "1") (pintype "passive"))
      (node (ref "C182") (pin "2") (pintype "passive"))
      (node (ref "C184") (pin "1") (pintype "passive"))
      (node (ref "C185") (pin "1") (pintype "passive"))
      (node (ref "C186") (pin "1") (pintype "passive"))
      (node (ref "C187") (pin "1") (pintype "passive"))
      (node (ref "C188") (pin "1") (pintype "passive"))
      (node (ref "C189") (pin "1") (pintype "passive"))
      (node (ref "C190") (pin "2") (pintype "passive"))
      (node (ref "C191") (pin "1") (pintype "passive"))
      (node (ref "C192") (pin "1") (pintype "passive"))
      (node (ref "C193") (pin "2") (pintype "passive"))
      (node (ref "C194") (pin "1") (pintype "passive"))
      (node (ref "C195") (pin "1") (pintype "passive"))
      (node (ref "C197") (pin "1") (pintype "passive"))
      (node (ref "C198") (pin "2") (pintype "passive"))
      (node (ref "C199") (pin "1") (pintype "passive"))
      (node (ref "C200") (pin "1") (pintype "passive"))
      (node (ref "C258") (pin "1") (pintype "passive"))
      (node (ref "C259") (pin "1") (pintype "passive"))
      (node (ref "C261") (pin "1") (pintype "passive"))
      (node (ref "C262") (pin "2") (pintype "passive"))
      (node (ref "C268") (pin "1") (pintype "passive"))
      (node (ref "C269") (pin "1") (pintype "passive"))
      (node (ref "C270") (pin "1") (pintype "passive"))
      (node (ref "C273") (pin "1") (pintype "passive"))
      (node (ref "D12") (pin "2") (pinfunction "A_2") (pintype "power_in"))
      (node (ref "D13") (pin "2") (pinfunction "A_2") (pintype "power_in"))
      (node (ref "D19") (pin "2") (pinfunction "A_2") (pintype "power_in"))
      (node (ref "D20") (pin "2") (pinfunction "A_2") (pintype "power_in"))
      (node (ref "D21") (pin "2") (pinfunction "A_2") (pintype "power_in"))
      (node (ref "D22") (pin "2") (pinfunction "A_2") (pintype "power_in"))
      (node (ref "R100") (pin "2") (pintype "passive"))
      (node (ref "R110") (pin "1") (pintype "passive"))
      (node (ref "R111") (pin "1") (pintype "passive"))
      (node (ref "R112") (pin "1") (pintype "passive"))
      (node (ref "R115") (pin "2") (pintype "passive"))
      (node (ref "R116") (pin "2") (pintype "passive"))
      (node (ref "R121") (pin "2") (pintype "passive"))
      (node (ref "R122") (pin "2") (pintype "passive"))
      (node (ref "R126") (pin "1") (pintype "passive"))
      (node (ref "R127") (pin "2") (pintype "passive"))
      (node (ref "R129") (pin "1") (pintype "passive"))
      (node (ref "R99") (pin "2") (pintype "passive"))
      (node (ref "U31") (pin "11") (pinfunction "PowerPAD_11") (pintype "power_in"))
      (node (ref "U31") (pin "9") (pinfunction "VSS_9") (pintype "power_in"))
      (node (ref "U35") (pin "11") (pinfunction "PowerPAD_11") (pintype "power_in"))
      (node (ref "U35") (pin "9") (pinfunction "VSS_9") (pintype "power_in"))
      (node (ref "U37") (pin "2") (pinfunction "GND_2") (pintype "passive"))
      (node (ref "U37") (pin "4") (pinfunction "NC_4") (pintype "passive"))
      (node (ref "U38") (pin "11") (pinfunction "PowerPAD_11") (pintype "power_in"))
      (node (ref "U38") (pin "9") (pinfunction "VSS_9") (pintype "power_in"))
      (node (ref "U39") (pin "2") (pinfunction "GND_2") (pintype "passive"))
      (node (ref "U39") (pin "4") (pinfunction "NC_4") (pintype "passive"))
      (node (ref "U40") (pin "2") (pinfunction "GND_2") (pintype "passive"))
      (node (ref "U40") (pin "4") (pinfunction "NC_4") (pintype "passive"))
      (node (ref "U41") (pin "2") (pinfunction "V-_2") (pintype "passive"))
    )
    (net (code "31") (name "Net-(L6-Pad1)") (class "Default")
      (node (ref "L6") (pin "1") (pintype "passive"))
      (node (ref "R103") (pin "2") (pintype "passive"))
      (node (ref "R106") (pin "2") (pintype "passive"))
      (node (ref "R95") (pin "2") (pintype "passive"))
    )
    (net (code "32") (name "Net-(L8-Pad1)") (class "Default")
      (node (ref "L8") (pin "1") (pintype "passive"))
      (node (ref "R105") (pin "2") (pintype "passive"))
      (node (ref "R108") (pin "2") (pintype "passive"))
      (node (ref "R97") (pin "2") (pintype "passive"))
    )
    (net (code "33") (name "Net-(Q10-S-Pad1)") (class "Default")
      (node (ref "Q10") (pin "1") (pinfunction "S_1") (pintype "passive"))
      (node (ref "Q10") (pin "2") (pinfunction "S_2") (pintype "passive"))
      (node (ref "Q10") (pin "3") (pinfunction "S_3") (pintype "passive"))
      (node (ref "Q11") (pin "1") (pinfunction "S_1") (pintype "passive"))
      (node (ref "Q11") (pin "2") (pinfunction "S_2") (pintype "passive"))
      (node (ref "Q11") (pin "3") (pinfunction "S_3") (pintype "passive"))
      (node (ref "Q9") (pin "1") (pinfunction "S_1") (pintype "passive"))
      (node (ref "Q9") (pin "2") (pinfunction "S_2") (pintype "passive"))
      (node (ref "Q9") (pin "3") (pinfunction "S_3") (pintype "passive"))
      (node (ref "R124") (pin "2") (pintype "passive"))
      (node (ref "R126") (pin "2") (pintype "passive"))
    )
    (net (code "34") (name "Net-(U31-HB)") (class "Default")
      (node (ref "C172") (pin "1") (pintype "passive"))
      (node (ref "U31") (pin "2") (pinfunction "HB_2") (pintype "power_in"))
    )
    (net (code "35") (name "Net-(U31-HI)") (class "Default")
      (node (ref "C173") (pin "2") (pintype "passive"))
      (node (ref "R96") (pin "1") (pintype "passive"))
      (node (ref "U31") (pin "7") (pinfunction "HI_7") (pintype "passive"))
    )
    (net (code "36") (name "Net-(U31-HO)") (class "Default")
      (node (ref "R94") (pin "1") (pintype "passive"))
      (node (ref "U31") (pin "3") (pinfunction "HO_3") (pintype "output"))
    )
    (net (code "37") (name "Net-(U31-LI)") (class "Default")
      (node (ref "C174") (pin "2") (pintype "passive"))
      (node (ref "R98") (pin "1") (pintype "passive"))
      (node (ref "U31") (pin "8") (pinfunction "LI_8") (pintype "passive"))
    )
    (net (code "38") (name "Net-(U31-LO)") (class "Default")
      (node (ref "R101") (pin "2") (pintype "passive"))
      (node (ref "U31") (pin "10") (pinfunction "LO_10") (pintype "output"))
    )
    (net (code "39") (name "Net-(U35-HB)") (class "Default")
      (node (ref "C183") (pin "1") (pintype "passive"))
      (node (ref "U35") (pin "2") (pinfunction "HB_2") (pintype "power_in"))
    )
    (net (code "40") (name "Net-(U35-HI)") (class "Default")
      (node (ref "C187") (pin "2") (pintype "passive"))
      (node (ref "R113") (pin "1") (pintype "passive"))
      (node (ref "U35") (pin "7") (pinfunction "HI_7") (pintype "passive"))
    )
    (net (code "41") (name "Net-(U35-HO)") (class "Default")
      (node (ref "R109") (pin "1") (pintype "passive"))
      (node (ref "U35") (pin "3") (pinfunction "HO_3") (pintype "output"))
    )
    (net (code "42") (name "Net-(U35-LI)") (class "Default")
      (node (ref "C188") (pin "2") (pintype "passive"))
      (node (ref "R114") (pin "1") (pintype "passive"))
      (node (ref "U35") (pin "8") (pinfunction "LI_8") (pintype "passive"))
    )
    (net (code "43") (name "Net-(U35-LO)") (class "Default")
      (node (ref "R117") (pin "2") (pintype "passive"))
      (node (ref "U35") (pin "10") (pinfunction "LO_10") (pintype "output"))
    )
    (net (code "44") (name "Net-(U37-IN+)") (class "Default")
      (node (ref "C179") (pin "1") (pintype "passive"))
      (node (ref "R104") (pin "1") (pintype "passive"))
      (node (ref "U37") (pin "8") (pinfunction "IN+_8") (pintype "passive"))
    )
    (net (code "45") (name "Net-(U37-IN-)") (class "Default")
      (node (ref "C179") (pin "2") (pintype "passive"))
      (node (ref "R105") (pin "1") (pintype "passive"))
      (node (ref "U37") (pin "1") (pinfunction "IN-_1") (pintype "passive"))
    )
    (net (code "46") (name "Net-(U38-HB)") (class "Default")
      (node (ref "C196") (pin "1") (pintype "passive"))
      (node (ref "U38") (pin "2") (pinfunction "HB_2") (pintype "power_in"))
    )
    (net (code "47") (name "Net-(U38-HI)") (class "Default")
      (node (ref "C199") (pin "2") (pintype "passive"))
      (node (ref "R119") (pin "1") (pintype "passive"))
      (node (ref "U38") (pin "7") (pinfunction "HI_7") (pintype "passive"))
    )
    (net (code "48") (name "Net-(U38-HO)") (class "Default")
      (node (ref "R118") (pin "1") (pintype "passive"))
      (node (ref "U38") (pin "3") (pinfunction "HO_3") (pintype "output"))
    )
    (net (code "49") (name "Net-(U38-LI)") (class "Default")
      (node (ref "C200") (pin "2") (pintype "passive"))
      (node (ref "R120") (pin "1") (pintype "passive"))
      (node (ref "U38") (pin "8") (pinfunction "LI_8") (pintype "passive"))
    )
    (net (code "50") (name "Net-(U38-LO)") (class "Default")
      (node (ref "R123") (pin "2") (pintype "passive"))
      (node (ref "U38") (pin "10") (pinfunction "LO_10") (pintype "output"))
    )
    (net (code "51") (name "Net-(U39-IN+)") (class "Default")
      (node (ref "C178") (pin "1") (pintype "passive"))
      (node (ref "R102") (pin "1") (pintype "passive"))
      (node (ref "U39") (pin "8") (pinfunction "IN+_8") (pintype "passive"))
    )
    (net (code "52") (name "Net-(U39-IN-)") (class "Default")
      (node (ref "C178") (pin "2") (pintype "passive"))
      (node (ref "R103") (pin "1") (pintype "passive"))
      (node (ref "U39") (pin "1") (pinfunction "IN-_1") (pintype "passive"))
    )
    (net (code "53") (name "Net-(U40-IN+)") (class "Default")
      (node (ref "C267") (pin "2") (pintype "passive"))
      (node (ref "R124") (pin "1") (pintype "passive"))
      (node (ref "U40") (pin "8") (pinfunction "IN+_8") (pintype "passive"))
    )
    (net (code "54") (name "Net-(U40-IN-)") (class "Default")
      (node (ref "C267") (pin "1") (pintype "passive"))
      (node (ref "R127") (pin "1") (pintype "passive"))
      (node (ref "U40") (pin "1") (pinfunction "IN-_1") (pintype "passive"))
    )
    (net (code "55") (name "Net-(U40-OUT)") (class "Default")
      (node (ref "R125") (pin "2") (pintype "passive"))
      (node (ref "U40") (pin "5") (pinfunction "OUT_5") (pintype "passive"))
    )
    (net (code "56") (name "OC_VREF") (class "Default")
      (node (ref "C270") (pin "2") (pintype "passive"))
      (node (ref "R128") (pin "1") (pintype "passive"))
      (node (ref "R129") (pin "2") (pintype "passive"))
      (node (ref "U41") (pin "3") (pinfunction "IN-_3") (pintype "passive"))
    )
    (net (code "57") (name "VBUS") (class "Default")
      (node (ref "C159") (pin "2") (pintype "passive"))
      (node (ref "C160") (pin "2") (pintype "passive"))
      (node (ref "C161") (pin "2") (pintype "passive"))
      (node (ref "C162") (pin "2") (pintype "passive"))
      (node (ref "C163") (pin "2") (pintype "passive"))
      (node (ref "C164") (pin "2") (pintype "passive"))
      (node (ref "C165") (pin "2") (pintype "passive"))
      (node (ref "C166") (pin "2") (pintype "passive"))
      (node (ref "C167") (pin "2") (pintype "passive"))
      (node (ref "C168") (pin "2") (pintype "passive"))
      (node (ref "Q6") (pin "5") (pinfunction "D_5") (pintype "passive"))
      (node (ref "Q6") (pin "6") (pinfunction "D_6") (pintype "passive"))
      (node (ref "Q6") (pin "7") (pinfunction "D_7") (pintype "passive"))
      (node (ref "Q6") (pin "8") (pinfunction "D_8") (pintype "passive"))
      (node (ref "Q7") (pin "5") (pinfunction "D_5") (pintype "passive"))
      (node (ref "Q7") (pin "6") (pinfunction "D_6") (pintype "passive"))
      (node (ref "Q7") (pin "7") (pinfunction "D_7") (pintype "passive"))
      (node (ref "Q7") (pin "8") (pinfunction "D_8") (pintype "passive"))
      (node (ref "Q8") (pin "5") (pinfunction "D_5") (pintype "passive"))
      (node (ref "Q8") (pin "6") (pinfunction "D_6") (pintype "passive"))
      (node (ref "Q8") (pin "7") (pinfunction "D_7") (pintype "passive"))
      (node (ref "Q8") (pin "8") (pinfunction "D_8") (pintype "passive"))
    )
    (net (code "58") (name "unconnected-(U31-NC-Pad5)") (class "Default")
      (node (ref "U31") (pin "5") (pinfunction "NC_5") (pintype "passive+no_connect"))
    )
    (net (code "59") (name "unconnected-(U31-NC-Pad6)") (class "Default")
      (node (ref "U31") (pin "6") (pinfunction "NC_6") (pintype "passive+no_connect"))
    )
    (net (code "60") (name "unconnected-(U35-NC-Pad5)") (class "Default")
      (node (ref "U35") (pin "5") (pinfunction "NC_5") (pintype "passive+no_connect"))
    )
    (net (code "61") (name "unconnected-(U35-NC-Pad6)") (class "Default")
      (node (ref "U35") (pin "6") (pinfunction "NC_6") (pintype "passive+no_connect"))
    )
    (net (code "62") (name "unconnected-(U38-NC-Pad5)") (class "Default")
      (node (ref "U38") (pin "5") (pinfunction "NC_5") (pintype "passive+no_connect"))
    )
    (net (code "63") (name "unconnected-(U38-NC-Pad6)") (class "Default")
      (node (ref "U38") (pin "6") (pinfunction "NC_6") (pintype "passive+no_connect"))
    )
  )
)
